# 03-Batteries.net
KiCad netlist of a schematic drawn in Altium Designer
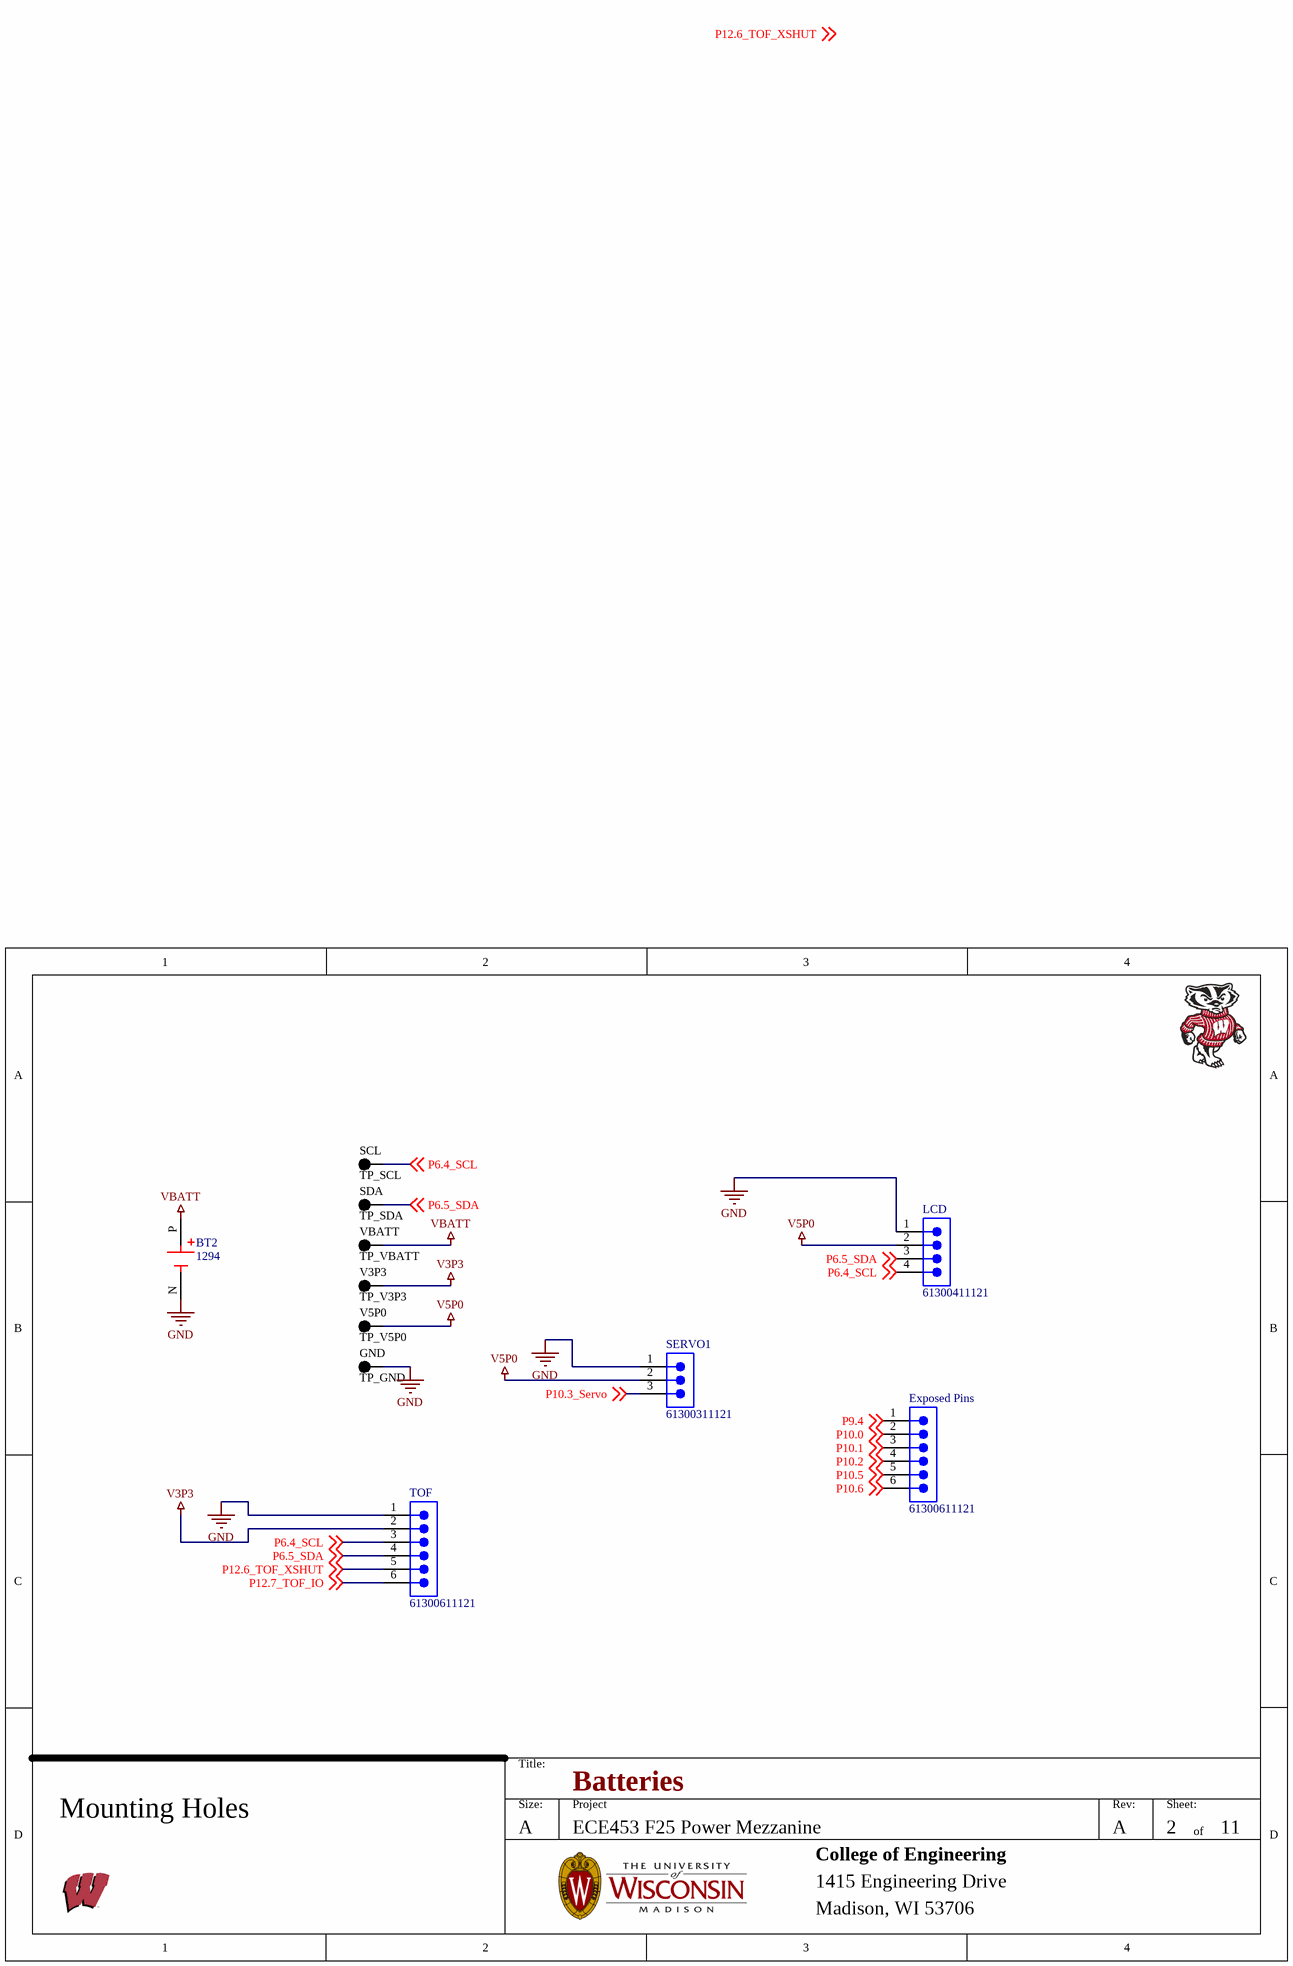
[diagram p0: 03-Batteries.SchDoc]

(export (version "E")
  (design (tool "Eeschema 10.0.6"))
  (components
    (comp (ref "BT2")
      (value "1294")
      (footprint "BAT_1294")
      (description "Batteries/Accessories")
      (fields (field (name "MF") "Keystone Electronics"))
      (libsource (lib "uw-madison-parts") (part "1294"))
    )
    (comp (ref "Exposed Pins")
      (value "61300611121")
      (footprint "61300611121")
      (libsource (lib "Altium Content Vault") (part "Header_Male_1R_06P"))
    )
    (comp (ref "GND")
      (value "TP_GND")
      (footprint "KSTN-5011_V")
      (description "Test Point, Black, Through Hole, RoHS, Bulk")
      (fields (field (name "MANUFACTURER") "Keystone"))
      (libsource (lib "Altium Content Vault") (part "TESTPOINT_BLACK"))
    )
    (comp (ref "LCD")
      (value "61300411121")
      (footprint "61300411121")
      (libsource (lib "Altium Content Vault") (part "Header_Male_1R_04P"))
    )
    (comp (ref "SCL")
      (value "TP_SCL")
      (footprint "KSTN-5011_V")
      (description "Test Point, Black, Through Hole, RoHS, Bulk")
      (fields (field (name "MANUFACTURER") "Keystone"))
      (libsource (lib "Altium Content Vault") (part "TESTPOINT_BLACK"))
    )
    (comp (ref "SDA")
      (value "TP_SDA")
      (footprint "KSTN-5011_V")
      (description "Test Point, Black, Through Hole, RoHS, Bulk")
      (fields (field (name "MANUFACTURER") "Keystone"))
      (libsource (lib "Altium Content Vault") (part "TESTPOINT_BLACK"))
    )
    (comp (ref "SERVO1")
      (value "61300311121")
      (footprint "61300311121")
      (libsource (lib "Altium Content Vault") (part "Header_Male_1R_03P"))
    )
    (comp (ref "TOF")
      (value "61300611121")
      (footprint "61300611121")
      (libsource (lib "Altium Content Vault") (part "Header_Male_1R_06P"))
    )
    (comp (ref "V3P3")
      (value "TP_V3P3")
      (footprint "KSTN-5011_V")
      (description "Test Point, Black, Through Hole, RoHS, Bulk")
      (fields (field (name "MANUFACTURER") "Keystone"))
      (libsource (lib "Altium Content Vault") (part "TESTPOINT_BLACK"))
    )
    (comp (ref "V5P0")
      (value "TP_V5P0")
      (footprint "KSTN-5011_V")
      (description "Test Point, Black, Through Hole, RoHS, Bulk")
      (fields (field (name "MANUFACTURER") "Keystone"))
      (libsource (lib "Altium Content Vault") (part "TESTPOINT_BLACK"))
    )
    (comp (ref "VBATT")
      (value "TP_VBATT")
      (footprint "KSTN-5011_V")
      (description "Test Point, Black, Through Hole, RoHS, Bulk")
      (fields (field (name "MANUFACTURER") "Keystone"))
      (libsource (lib "Altium Content Vault") (part "TESTPOINT_BLACK"))
    )
  )
  (nets
    (net (code "1") (name "GND") (class "Default")
      (node (ref "BT2") (pin "N") (pinfunction "NEG_N") (pintype "passive"))
      (node (ref "GND") (pin "1") (pinfunction "1_1") (pintype "passive"))
      (node (ref "LCD") (pin "1") (pinfunction "1_1") (pintype "passive"))
      (node (ref "SERVO1") (pin "1") (pinfunction "1_1") (pintype "passive"))
      (node (ref "TOF") (pin "1") (pinfunction "1_1") (pintype "passive"))
    )
    (net (code "2") (name "P6.4_SCL") (class "Default")
      (node (ref "LCD") (pin "4") (pinfunction "4_4") (pintype "passive"))
      (node (ref "SCL") (pin "1") (pinfunction "1_1") (pintype "passive"))
      (node (ref "TOF") (pin "3") (pinfunction "3_3") (pintype "passive"))
    )
    (net (code "3") (name "P6.5_SDA") (class "Default")
      (node (ref "LCD") (pin "3") (pinfunction "3_3") (pintype "passive"))
      (node (ref "SDA") (pin "1") (pinfunction "1_1") (pintype "passive"))
      (node (ref "TOF") (pin "4") (pinfunction "4_4") (pintype "passive"))
    )
    (net (code "4") (name "P9.4") (class "Default")
      (node (ref "Exposed Pins") (pin "1") (pinfunction "1_1") (pintype "passive"))
    )
    (net (code "5") (name "P10.0") (class "Default")
      (node (ref "Exposed Pins") (pin "2") (pinfunction "2_2") (pintype "passive"))
    )
    (net (code "6") (name "P10.1") (class "Default")
      (node (ref "Exposed Pins") (pin "3") (pinfunction "3_3") (pintype "passive"))
    )
    (net (code "7") (name "P10.2") (class "Default")
      (node (ref "Exposed Pins") (pin "4") (pinfunction "4_4") (pintype "passive"))
    )
    (net (code "8") (name "P10.3_Servo") (class "Default")
      (node (ref "SERVO1") (pin "3") (pinfunction "3_3") (pintype "passive"))
    )
    (net (code "9") (name "P10.5") (class "Default")
      (node (ref "Exposed Pins") (pin "5") (pinfunction "5_5") (pintype "passive"))
    )
    (net (code "10") (name "P10.6") (class "Default")
      (node (ref "Exposed Pins") (pin "6") (pinfunction "6_6") (pintype "passive"))
    )
    (net (code "11") (name "P12.6_TOF_XSHUT") (class "Default")
      (node (ref "TOF") (pin "5") (pinfunction "5_5") (pintype "passive"))
    )
    (net (code "12") (name "P12.7_TOF_IO") (class "Default")
      (node (ref "TOF") (pin "6") (pinfunction "6_6") (pintype "passive"))
    )
    (net (code "13") (name "V3P3") (class "Default")
      (node (ref "TOF") (pin "2") (pinfunction "2_2") (pintype "passive"))
      (node (ref "V3P3") (pin "1") (pinfunction "1_1") (pintype "passive"))
    )
    (net (code "14") (name "V5P0") (class "Default")
      (node (ref "LCD") (pin "2") (pinfunction "2_2") (pintype "passive"))
      (node (ref "SERVO1") (pin "2") (pinfunction "2_2") (pintype "passive"))
      (node (ref "V5P0") (pin "1") (pinfunction "1_1") (pintype "passive"))
    )
    (net (code "15") (name "VBATT") (class "Default")
      (node (ref "BT2") (pin "P") (pinfunction "POS_P") (pintype "passive"))
      (node (ref "VBATT") (pin "1") (pinfunction "1_1") (pintype "passive"))
    )
  )
)
